# LEDCLOCK.net
KiCad netlist of a schematic drawn in EAGLE
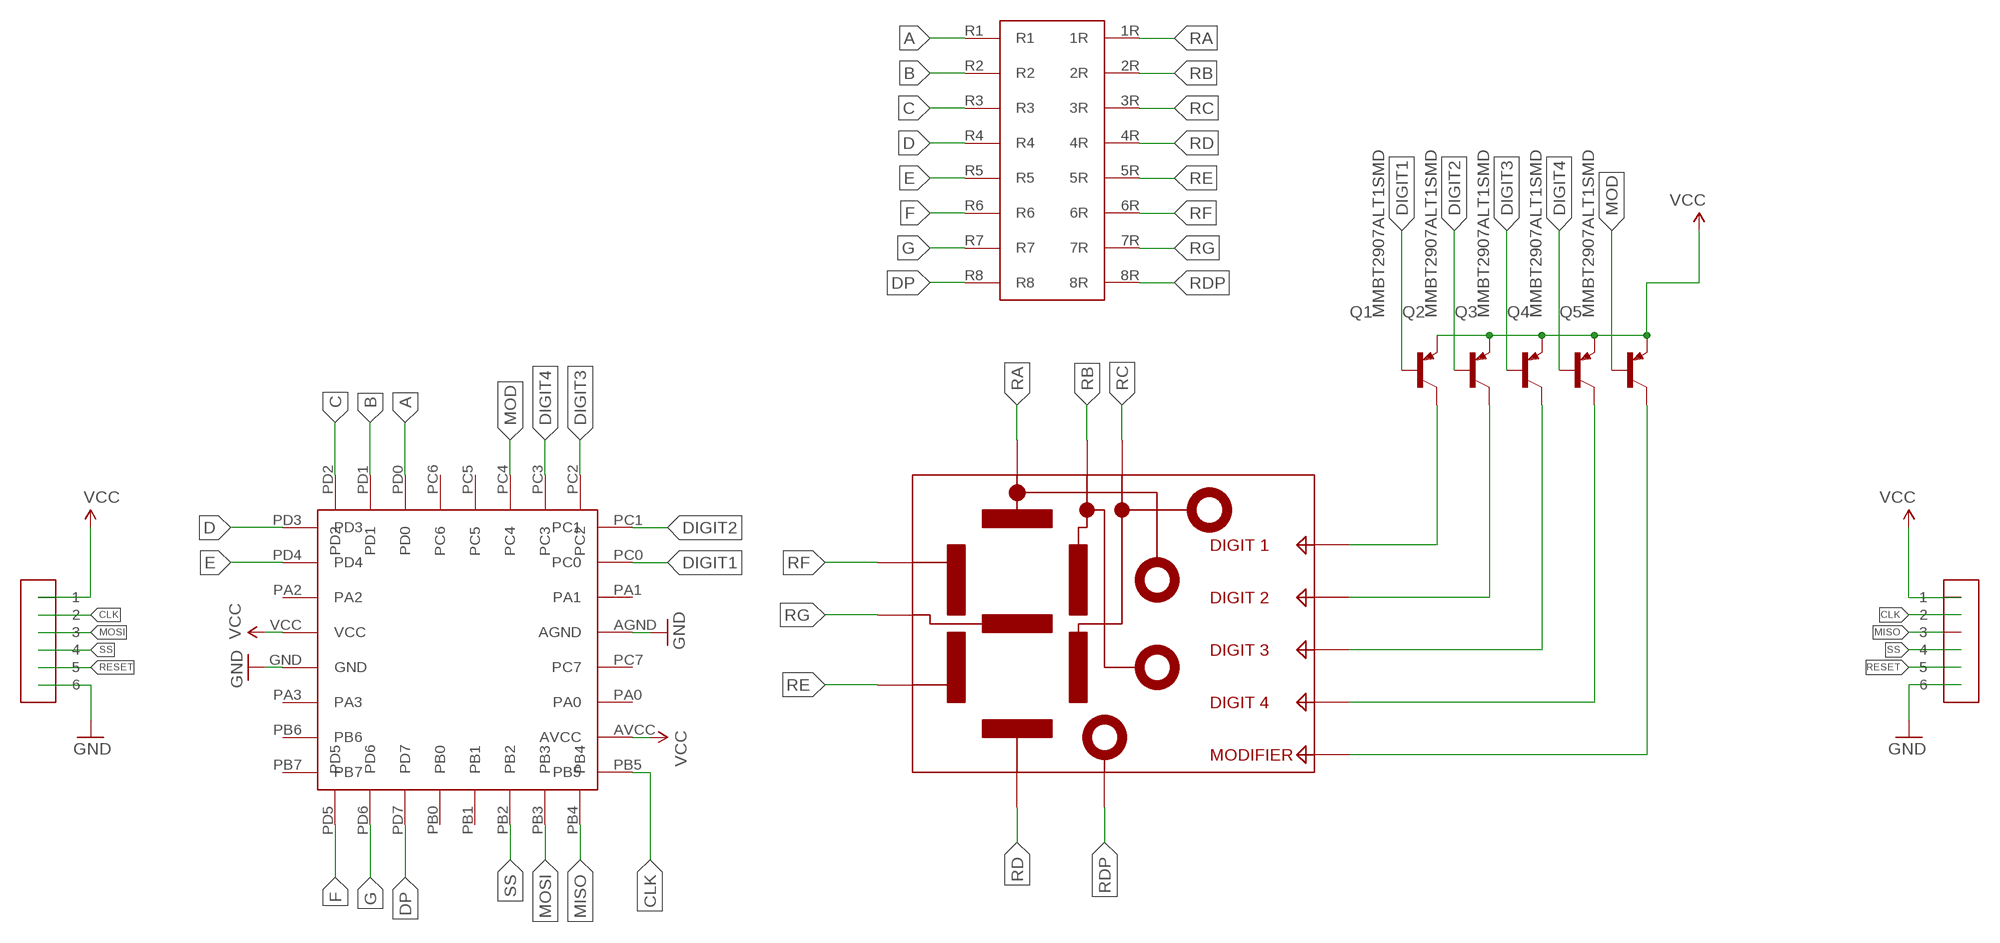
[diagram p0: schematic, sheet 1]

(export (version "E")
  (design (tool "Eeschema 10.0.6"))
  (components
    (comp (ref "Q1")
      (value "MMBT2907ALT1SMD")
      (footprint "eagle-import:SOT23-BEC")
      (libsource (lib "eagle-import") (part "MMBT2907SMDALT1"))
    )
    (comp (ref "Q2")
      (value "MMBT2907ALT1SMD")
      (footprint "eagle-import:SOT23-BEC")
      (libsource (lib "eagle-import") (part "MMBT2907SMDALT1"))
    )
    (comp (ref "Q3")
      (value "MMBT2907ALT1SMD")
      (footprint "eagle-import:SOT23-BEC")
      (libsource (lib "eagle-import") (part "MMBT2907SMDALT1"))
    )
    (comp (ref "Q4")
      (value "MMBT2907ALT1SMD")
      (footprint "eagle-import:SOT23-BEC")
      (libsource (lib "eagle-import") (part "MMBT2907SMDALT1"))
    )
    (comp (ref "Q5")
      (value "MMBT2907ALT1SMD")
      (footprint "eagle-import:SOT23-BEC")
      (libsource (lib "eagle-import") (part "MMBT2907SMDALT1"))
    )
    (comp (ref "U$1")
      (value "LEDCLOCK")
      (footprint "eagle-import:LEDCLOCK")
      (libsource (lib "eagle-import") (part "LEDCLOCK"))
    )
    (comp (ref "U$2")
      (value "DIP1X6MALE")
      (footprint "eagle-import:DIP1X6MALE")
      (libsource (lib "eagle-import") (part "DIP1X6MALE"))
    )
    (comp (ref "U$3")
      (value "RES_ARRAY")
      (footprint "eagle-import:RES_ARRAY")
      (libsource (lib "eagle-import") (part "RES_ARRAY"))
    )
    (comp (ref "U$4")
      (value "DIP1X6MALE")
      (footprint "eagle-import:DIP1X6MALE")
      (libsource (lib "eagle-import") (part "DIP1X6MALE"))
    )
    (comp (ref "U$5")
      (value "ATTINY48")
      (footprint "eagle-import:ATTINY48")
      (libsource (lib "eagle-import") (part "ATTINY48"))
    )
  )
  (nets
    (net (code "1") (name "A") (class "Default")
      (node (ref "U$3") (pin "R1") (pinfunction "R1_R1") (pintype "bidirectional"))
      (node (ref "U$5") (pin "PD0") (pinfunction "PD0_PD0") (pintype "bidirectional"))
    )
    (net (code "2") (name "B") (class "Default")
      (node (ref "U$3") (pin "R2") (pinfunction "R2_R2") (pintype "bidirectional"))
      (node (ref "U$5") (pin "PD1") (pinfunction "PD1_PD1") (pintype "bidirectional"))
    )
    (net (code "3") (name "C") (class "Default")
      (node (ref "U$3") (pin "R3") (pinfunction "R3_R3") (pintype "bidirectional"))
      (node (ref "U$5") (pin "PD2") (pinfunction "PD2_PD2") (pintype "bidirectional"))
    )
    (net (code "4") (name "CLK") (class "Default")
      (node (ref "U$2") (pin "2") (pinfunction "2_2") (pintype "bidirectional"))
      (node (ref "U$4") (pin "2") (pinfunction "2_2") (pintype "bidirectional"))
      (node (ref "U$5") (pin "PB5") (pinfunction "PB5_PB5") (pintype "bidirectional"))
    )
    (net (code "5") (name "D") (class "Default")
      (node (ref "U$3") (pin "R4") (pinfunction "R4_R4") (pintype "bidirectional"))
      (node (ref "U$5") (pin "PD3") (pinfunction "PD3_PD3") (pintype "bidirectional"))
    )
    (net (code "6") (name "DIGIT1") (class "Default")
      (node (ref "Q1") (pin "B") (pinfunction "B_B") (pintype "passive"))
      (node (ref "U$5") (pin "PC0") (pinfunction "PC0_PC0") (pintype "bidirectional"))
    )
    (net (code "7") (name "DIGIT2") (class "Default")
      (node (ref "Q2") (pin "B") (pinfunction "B_B") (pintype "passive"))
      (node (ref "U$5") (pin "PC1") (pinfunction "PC1_PC1") (pintype "bidirectional"))
    )
    (net (code "8") (name "DIGIT3") (class "Default")
      (node (ref "Q3") (pin "B") (pinfunction "B_B") (pintype "passive"))
      (node (ref "U$5") (pin "PC2") (pinfunction "PC2_PC2") (pintype "bidirectional"))
    )
    (net (code "9") (name "DIGIT4") (class "Default")
      (node (ref "Q4") (pin "B") (pinfunction "B_B") (pintype "passive"))
      (node (ref "U$5") (pin "PC3") (pinfunction "PC3_PC3") (pintype "bidirectional"))
    )
    (net (code "10") (name "DP") (class "Default")
      (node (ref "U$3") (pin "R8") (pinfunction "R8_R8") (pintype "bidirectional"))
      (node (ref "U$5") (pin "PD7") (pinfunction "PD7_PD7") (pintype "bidirectional"))
    )
    (net (code "11") (name "E") (class "Default")
      (node (ref "U$3") (pin "R5") (pinfunction "R5_R5") (pintype "bidirectional"))
      (node (ref "U$5") (pin "PD4") (pinfunction "PD4_PD4") (pintype "bidirectional"))
    )
    (net (code "12") (name "F") (class "Default")
      (node (ref "U$3") (pin "R6") (pinfunction "R6_R6") (pintype "bidirectional"))
      (node (ref "U$5") (pin "PD5") (pinfunction "PD5_PD5") (pintype "bidirectional"))
    )
    (net (code "13") (name "G") (class "Default")
      (node (ref "U$3") (pin "R7") (pinfunction "R7_R7") (pintype "bidirectional"))
      (node (ref "U$5") (pin "PD6") (pinfunction "PD6_PD6") (pintype "bidirectional"))
    )
    (net (code "14") (name "GND") (class "Default")
      (node (ref "U$2") (pin "6") (pinfunction "6_6") (pintype "bidirectional"))
      (node (ref "U$4") (pin "6") (pinfunction "6_6") (pintype "bidirectional"))
      (node (ref "U$5") (pin "AGND") (pinfunction "AGND_AGND") (pintype "bidirectional"))
      (node (ref "U$5") (pin "GND") (pinfunction "GND_GND") (pintype "bidirectional"))
    )
    (net (code "15") (name "MISO") (class "Default")
      (node (ref "U$5") (pin "PB4") (pinfunction "PB4_PB4") (pintype "bidirectional"))
    )
    (net (code "16") (name "MOD") (class "Default")
      (node (ref "Q5") (pin "B") (pinfunction "B_B") (pintype "passive"))
      (node (ref "U$5") (pin "PC4") (pinfunction "PC4_PC4") (pintype "bidirectional"))
    )
    (net (code "17") (name "MOSI") (class "Default")
      (node (ref "U$2") (pin "3") (pinfunction "3_3") (pintype "bidirectional"))
      (node (ref "U$5") (pin "PB3") (pinfunction "PB3_PB3") (pintype "bidirectional"))
    )
    (net (code "18") (name "Net-(U$1-DIGIT1)") (class "Default")
      (node (ref "Q1") (pin "C") (pinfunction "C_C") (pintype "passive"))
      (node (ref "U$1") (pin "1") (pinfunction "DIGIT1_1") (pintype "bidirectional"))
    )
    (net (code "19") (name "Net-(U$1-DIGIT2)") (class "Default")
      (node (ref "Q2") (pin "C") (pinfunction "C_C") (pintype "passive"))
      (node (ref "U$1") (pin "2") (pinfunction "DIGIT2_2") (pintype "bidirectional"))
    )
    (net (code "20") (name "Net-(U$1-DIGIT3)") (class "Default")
      (node (ref "Q3") (pin "C") (pinfunction "C_C") (pintype "passive"))
      (node (ref "U$1") (pin "6") (pinfunction "DIGIT3_6") (pintype "bidirectional"))
    )
    (net (code "21") (name "Net-(U$1-DIGIT4)") (class "Default")
      (node (ref "Q4") (pin "C") (pinfunction "C_C") (pintype "passive"))
      (node (ref "U$1") (pin "8") (pinfunction "DIGIT4_8") (pintype "bidirectional"))
    )
    (net (code "22") (name "Net-(U$1-MOD)") (class "Default")
      (node (ref "Q5") (pin "C") (pinfunction "C_C") (pintype "passive"))
      (node (ref "U$1") (pin "4") (pinfunction "MOD_4") (pintype "bidirectional"))
    )
    (net (code "23") (name "RA") (class "Default")
      (node (ref "U$1") (pin "14") (pinfunction "A_14") (pintype "bidirectional"))
      (node (ref "U$3") (pin "1R") (pinfunction "1R_1R") (pintype "bidirectional"))
    )
    (net (code "24") (name "RB") (class "Default")
      (node (ref "U$1") (pin "16") (pinfunction "B_16") (pintype "bidirectional"))
      (node (ref "U$3") (pin "2R") (pinfunction "2R_2R") (pintype "bidirectional"))
    )
    (net (code "25") (name "RC") (class "Default")
      (node (ref "U$1") (pin "13") (pinfunction "C_13") (pintype "bidirectional"))
      (node (ref "U$3") (pin "3R") (pinfunction "3R_3R") (pintype "bidirectional"))
    )
    (net (code "26") (name "RD") (class "Default")
      (node (ref "U$1") (pin "3") (pinfunction "D_3") (pintype "bidirectional"))
      (node (ref "U$3") (pin "4R") (pinfunction "4R_4R") (pintype "bidirectional"))
    )
    (net (code "27") (name "RDP") (class "Default")
      (node (ref "U$1") (pin "7") (pinfunction "DP_7") (pintype "bidirectional"))
      (node (ref "U$3") (pin "8R") (pinfunction "8R_8R") (pintype "bidirectional"))
    )
    (net (code "28") (name "RE") (class "Default")
      (node (ref "U$1") (pin "5") (pinfunction "E_5") (pintype "bidirectional"))
      (node (ref "U$3") (pin "5R") (pinfunction "5R_5R") (pintype "bidirectional"))
    )
    (net (code "29") (name "RESET") (class "Default")
      (node (ref "U$2") (pin "5") (pinfunction "5_5") (pintype "bidirectional"))
      (node (ref "U$4") (pin "5") (pinfunction "5_5") (pintype "bidirectional"))
    )
    (net (code "30") (name "RF") (class "Default")
      (node (ref "U$1") (pin "11") (pinfunction "F_11") (pintype "bidirectional"))
      (node (ref "U$3") (pin "6R") (pinfunction "6R_6R") (pintype "bidirectional"))
    )
    (net (code "31") (name "RG") (class "Default")
      (node (ref "U$1") (pin "15") (pinfunction "G_15") (pintype "bidirectional"))
      (node (ref "U$3") (pin "7R") (pinfunction "7R_7R") (pintype "bidirectional"))
    )
    (net (code "32") (name "SS") (class "Default")
      (node (ref "U$2") (pin "4") (pinfunction "4_4") (pintype "bidirectional"))
      (node (ref "U$4") (pin "4") (pinfunction "4_4") (pintype "bidirectional"))
      (node (ref "U$5") (pin "PB2") (pinfunction "PB2_PB2") (pintype "bidirectional"))
    )
    (net (code "33") (name "VCC") (class "Default")
      (node (ref "Q1") (pin "E") (pinfunction "E_E") (pintype "passive"))
      (node (ref "Q2") (pin "E") (pinfunction "E_E") (pintype "passive"))
      (node (ref "Q3") (pin "E") (pinfunction "E_E") (pintype "passive"))
      (node (ref "Q4") (pin "E") (pinfunction "E_E") (pintype "passive"))
      (node (ref "Q5") (pin "E") (pinfunction "E_E") (pintype "passive"))
      (node (ref "U$2") (pin "1") (pinfunction "1_1") (pintype "bidirectional"))
      (node (ref "U$4") (pin "1") (pinfunction "1_1") (pintype "bidirectional"))
      (node (ref "U$5") (pin "AVCC") (pinfunction "AVCC_AVCC") (pintype "bidirectional"))
      (node (ref "U$5") (pin "VCC") (pinfunction "VCC_VCC") (pintype "bidirectional"))
    )
    (net (code "34") (name "unconnected-(U$4-Pad3)") (class "Default")
      (node (ref "U$4") (pin "3") (pinfunction "3_3") (pintype "bidirectional"))
    )
    (net (code "35") (name "unconnected-(U$5-PadPA0)") (class "Default")
      (node (ref "U$5") (pin "PA0") (pinfunction "PA0_PA0") (pintype "bidirectional"))
    )
    (net (code "36") (name "unconnected-(U$5-PadPA1)") (class "Default")
      (node (ref "U$5") (pin "PA1") (pinfunction "PA1_PA1") (pintype "bidirectional"))
    )
    (net (code "37") (name "unconnected-(U$5-PadPA2)") (class "Default")
      (node (ref "U$5") (pin "PA2") (pinfunction "PA2_PA2") (pintype "bidirectional"))
    )
    (net (code "38") (name "unconnected-(U$5-PadPA3)") (class "Default")
      (node (ref "U$5") (pin "PA3") (pinfunction "PA3_PA3") (pintype "bidirectional"))
    )
    (net (code "39") (name "unconnected-(U$5-PadPB0)") (class "Default")
      (node (ref "U$5") (pin "PB0") (pinfunction "PB0_PB0") (pintype "bidirectional"))
    )
    (net (code "40") (name "unconnected-(U$5-PadPB1)") (class "Default")
      (node (ref "U$5") (pin "PB1") (pinfunction "PB1_PB1") (pintype "bidirectional"))
    )
    (net (code "41") (name "unconnected-(U$5-PadPB6)") (class "Default")
      (node (ref "U$5") (pin "PB6") (pinfunction "PB6_PB6") (pintype "bidirectional"))
    )
    (net (code "42") (name "unconnected-(U$5-PadPB7)") (class "Default")
      (node (ref "U$5") (pin "PB7") (pinfunction "PB7_PB7") (pintype "bidirectional"))
    )
    (net (code "43") (name "unconnected-(U$5-PadPC5)") (class "Default")
      (node (ref "U$5") (pin "PC5") (pinfunction "PC5_PC5") (pintype "bidirectional"))
    )
    (net (code "44") (name "unconnected-(U$5-PadPC6)") (class "Default")
      (node (ref "U$5") (pin "PC6") (pinfunction "PC6_PC6") (pintype "bidirectional"))
    )
    (net (code "45") (name "unconnected-(U$5-PadPC7)") (class "Default")
      (node (ref "U$5") (pin "PC7") (pinfunction "PC7_PC7") (pintype "bidirectional"))
    )
  )
)
